# airPi_HV.net
KiCad netlist of a schematic drawn in Altium Designer
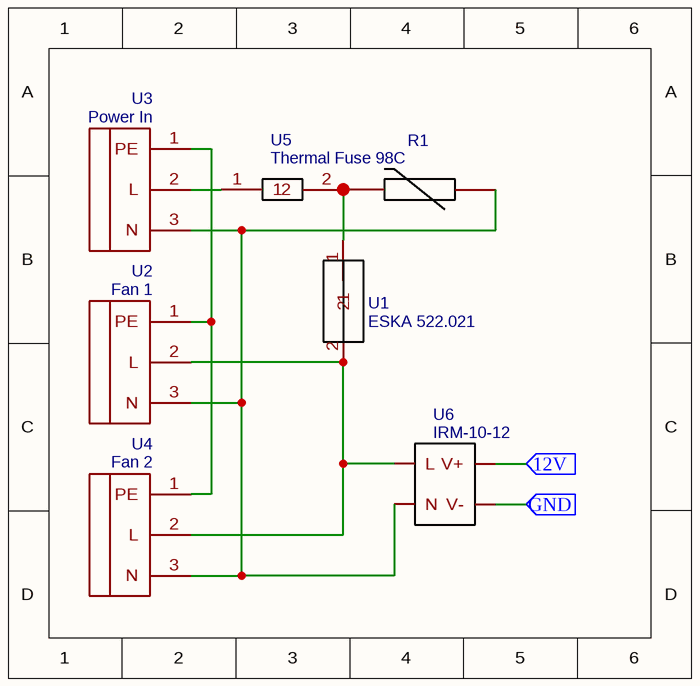
[diagram p0: airPi_HV.schdoc]

(export (version "E")
  (design (tool "Eeschema 10.0.6"))
  (components
    (comp (ref "R1")
      (value "Varistor")
      (fields
        (field (name "MANUFACTURER") "EPCOS - TDK Electronics")
        (field (name "MANUFACTURER PART") "B72220S0301K101")
        (field (name "CONTRIBUTOR") "johncurtin")
      )
      (libsource (lib "altium-import") (part "root_2_Varistor_"))
    )
    (comp (ref "U1")
      (value "ESKA 522.021")
      (fields (field (name "MANUFACTURER PART") "2050000172717") (field (name "CONTRIBUTOR") "Rhome"))
      (libsource (lib "altium-import") (part "root_3_ESKA 522.021_"))
    )
    (comp (ref "U2")
      (value "Fan 1")
      (fields
        (field (name "MANUFACTURER") "Phoenix Contact(菲尼克斯)")
        (field (name "MANUFACTURER PART") "MSTBA 2,5/ 3-G-5,08")
        (field (name "CONTRIBUTOR") "lcsc")
      )
      (libsource (lib "altium-import") (part "root_0_Fan 1_"))
    )
    (comp (ref "U3")
      (value "Power In")
      (fields
        (field (name "MANUFACTURER") "Phoenix Contact(菲尼克斯)")
        (field (name "MANUFACTURER PART") "MSTBA 2,5/ 3-G-5,08")
        (field (name "CONTRIBUTOR") "lcsc")
      )
      (libsource (lib "altium-import") (part "root_0_Power In_"))
    )
    (comp (ref "U4")
      (value "Fan 2")
      (fields
        (field (name "MANUFACTURER") "Phoenix Contact(菲尼克斯)")
        (field (name "MANUFACTURER PART") "MSTBA 2,5/ 3-G-5,08")
        (field (name "CONTRIBUTOR") "lcsc")
      )
      (libsource (lib "altium-import") (part "root_0_Fan 2_"))
    )
    (comp (ref "U5")
      (value "Thermal Fuse 98C")
      (fields
        (field (name "MANUFACTURER") "ESKA")
        (field (name "MANUFACTURER PART") "777.098")
        (field (name "CONTRIBUTOR") "ljeff")
      )
      (libsource (lib "altium-import") (part "root_0_Thermal Fuse 98C_"))
    )
    (comp (ref "U6")
      (value "IRM-10-12")
      (fields (field (name "MANUFACTURER") "MEAN WELL USA Inc.") (field (name "CONTRIBUTOR") "energybank"))
      (libsource (lib "altium-import") (part "root_0_IRM-10-12_"))
    )
  )
  (nets
    (net (code "1") (name "/12V") (class "Default")
      (node (ref "U6") (pin "V+") (pinfunction "V+_V+") (pintype "passive"))
    )
    (net (code "2") (name "/GND") (class "Default")
      (node (ref "U6") (pin "V-") (pinfunction "V-_V-") (pintype "passive"))
    )
    (net (code "3") (name "Net-(R1-Pad2)") (class "Default")
      (node (ref "R1") (pin "2") (pinfunction "2_2") (pintype "passive"))
      (node (ref "U1") (pin "1") (pinfunction "1_1") (pintype "passive"))
      (node (ref "U5") (pin "2") (pinfunction "2_2") (pintype "passive"))
    )
    (net (code "4") (name "Net-(U2-L)") (class "Default")
      (node (ref "U1") (pin "2") (pinfunction "2_2") (pintype "passive"))
      (node (ref "U2") (pin "2") (pinfunction "L_2") (pintype "passive"))
      (node (ref "U4") (pin "2") (pinfunction "L_2") (pintype "passive"))
      (node (ref "U6") (pin "L") (pinfunction "L_L") (pintype "passive"))
    )
    (net (code "5") (name "Net-(U2-N)") (class "Default")
      (node (ref "R1") (pin "1") (pinfunction "1_1") (pintype "passive"))
      (node (ref "U2") (pin "3") (pinfunction "N_3") (pintype "passive"))
      (node (ref "U3") (pin "3") (pinfunction "N_3") (pintype "passive"))
      (node (ref "U4") (pin "3") (pinfunction "N_3") (pintype "passive"))
      (node (ref "U6") (pin "N") (pinfunction "N_N") (pintype "passive"))
    )
    (net (code "6") (name "Net-(U2-PE)") (class "Default")
      (node (ref "U2") (pin "1") (pinfunction "PE_1") (pintype "passive"))
      (node (ref "U3") (pin "1") (pinfunction "PE_1") (pintype "passive"))
      (node (ref "U4") (pin "1") (pinfunction "PE_1") (pintype "passive"))
    )
    (net (code "7") (name "Net-(U3-L)") (class "Default")
      (node (ref "U3") (pin "2") (pinfunction "L_2") (pintype "passive"))
      (node (ref "U5") (pin "1") (pinfunction "1_1") (pintype "passive"))
    )
  )
)
